# BusPirate-v3_8a-SSOP.net
KiCad netlist of a schematic drawn in EAGLE
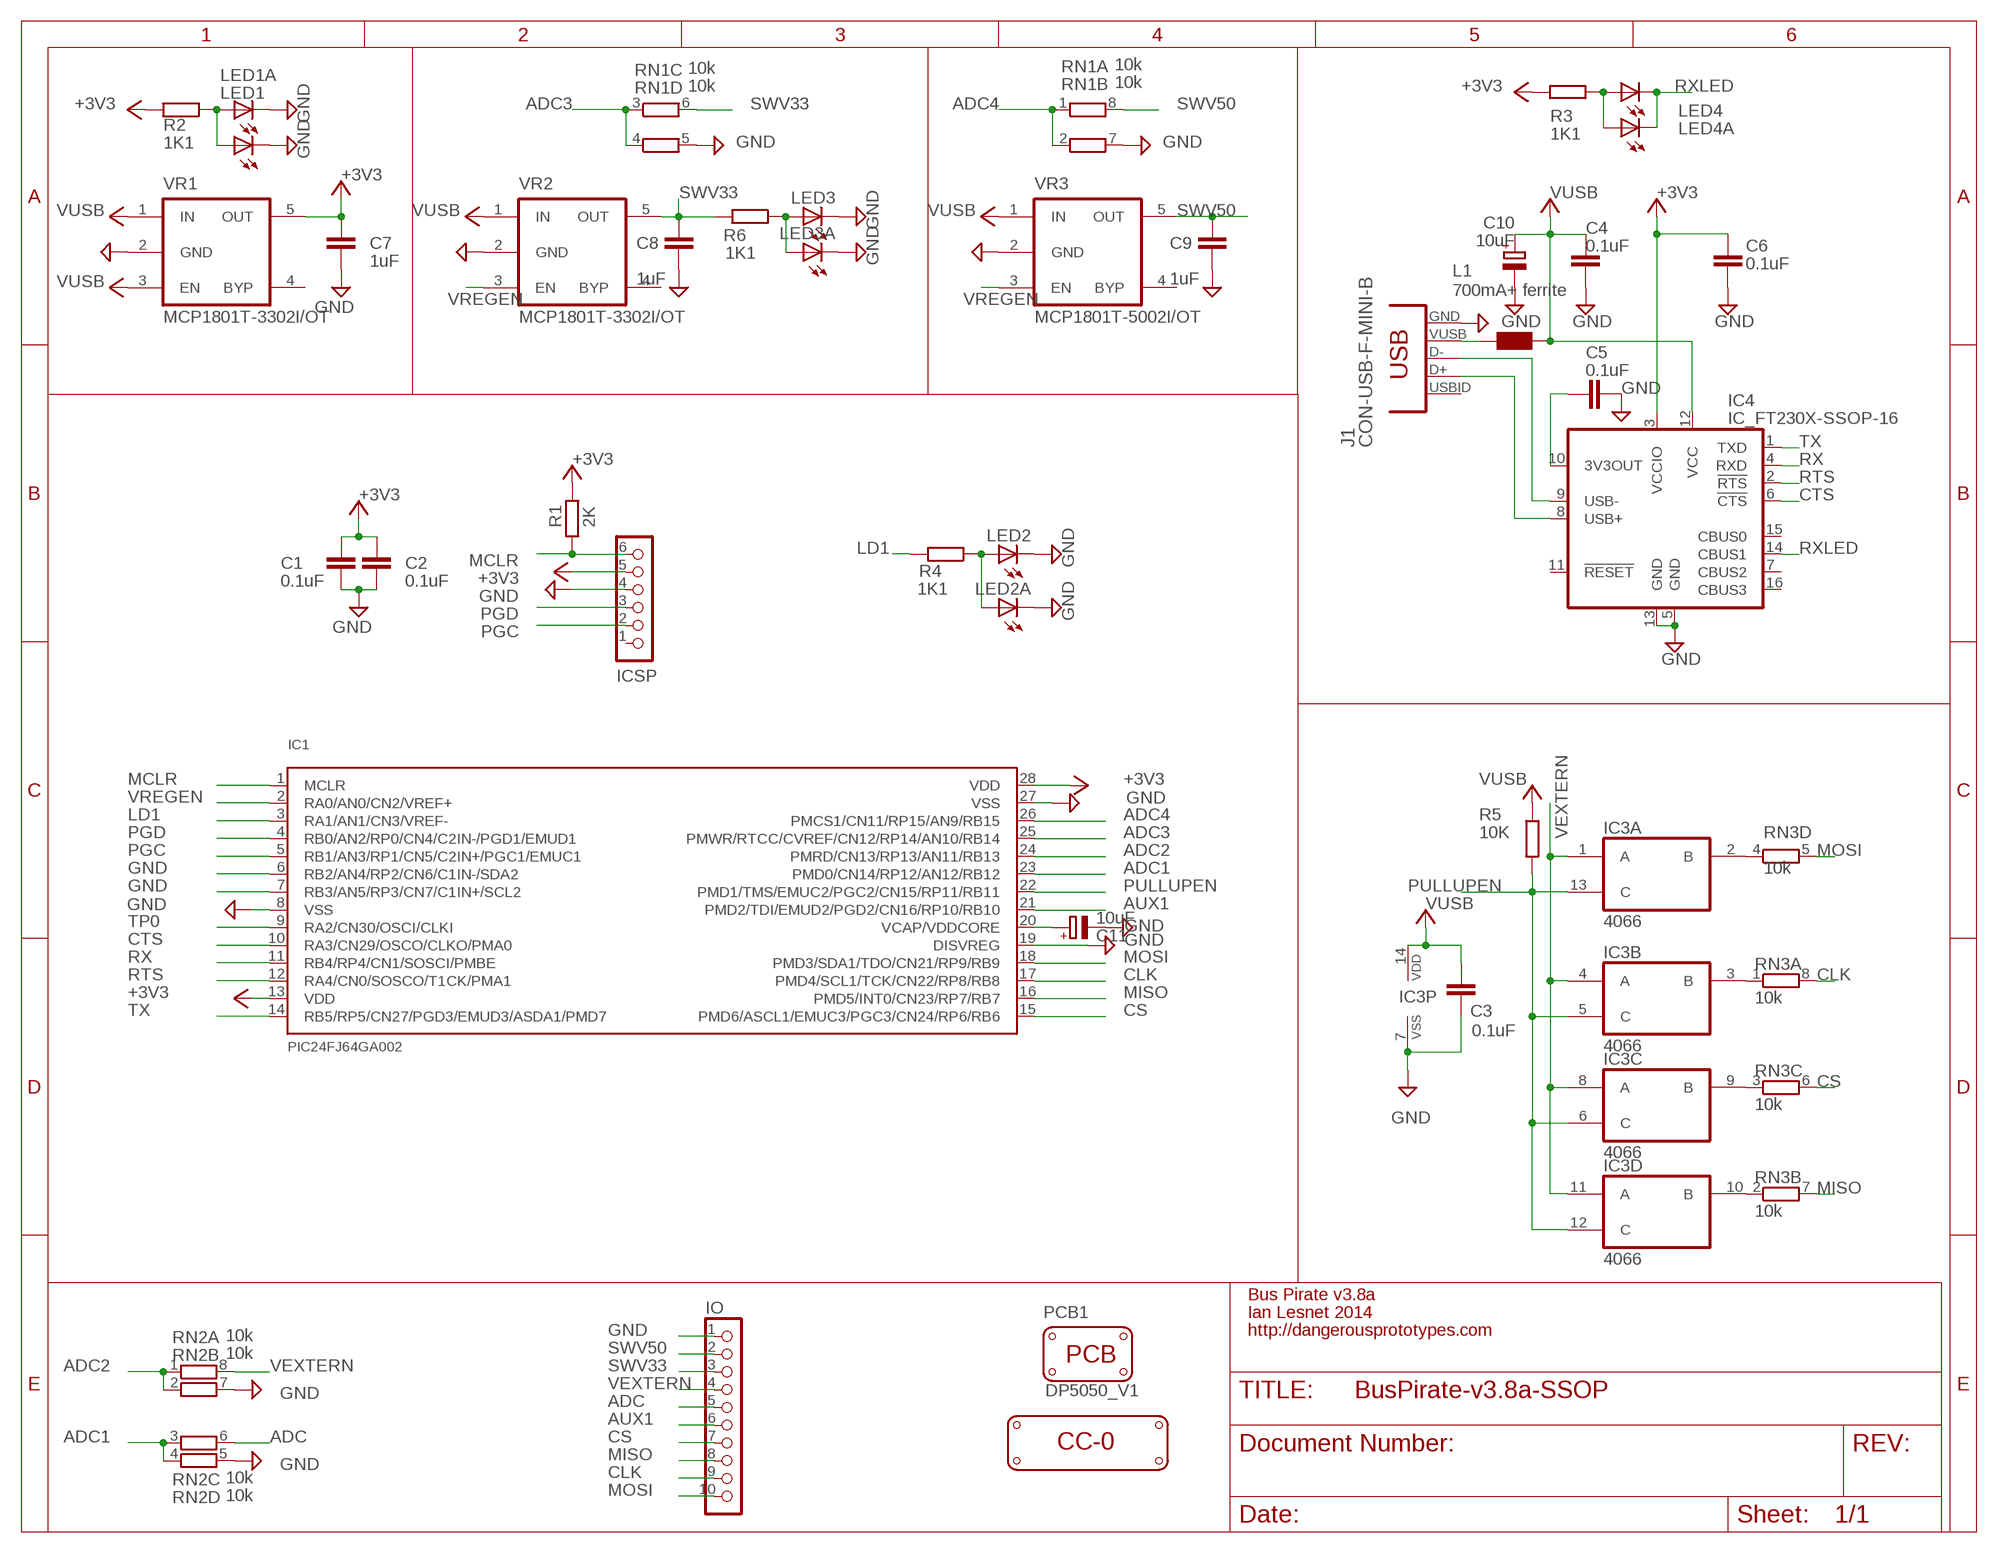
[diagram p0: schematic, sheet 1]

(export (version "E")
  (design (tool "Eeschema 10.0.6"))
  (components
    (comp (ref "C1")
      (value "0.1uF")
      (footprint "eagle-import:C603")
      (libsource (lib "eagle-import") (part "CAPC603"))
    )
    (comp (ref "C2")
      (value "0.1uF")
      (footprint "eagle-import:C603")
      (libsource (lib "eagle-import") (part "CAPC603"))
    )
    (comp (ref "C3")
      (value "0.1uF")
      (footprint "eagle-import:C603")
      (libsource (lib "eagle-import") (part "CAPC603"))
    )
    (comp (ref "C4")
      (value "0.1uF")
      (footprint "eagle-import:C603")
      (libsource (lib "eagle-import") (part "CAPC603"))
    )
    (comp (ref "C5")
      (value "0.1uF")
      (footprint "eagle-import:C603")
      (libsource (lib "eagle-import") (part "CAPC603"))
    )
    (comp (ref "C6")
      (value "0.1uF")
      (footprint "eagle-import:C603")
      (libsource (lib "eagle-import") (part "CAPC603"))
    )
    (comp (ref "C7")
      (value "1uF")
      (footprint "eagle-import:C603")
      (libsource (lib "eagle-import") (part "CAPC603"))
    )
    (comp (ref "C8")
      (value "1uF")
      (footprint "eagle-import:C603")
      (libsource (lib "eagle-import") (part "CAPC603"))
    )
    (comp (ref "C9")
      (value "1uF")
      (footprint "eagle-import:C603")
      (libsource (lib "eagle-import") (part "CAPC603"))
    )
    (comp (ref "C10")
      (value "10uF")
      (footprint "eagle-import:SMC_A")
      (libsource (lib "eagle-import") (part "CPOL-EUSMCA"))
    )
    (comp (ref "C11")
      (value "10uF")
      (footprint "eagle-import:SMC_A")
      (libsource (lib "eagle-import") (part "CPOL-EUSMCA"))
    )
    (comp (ref "IC1")
      (value "PIC24FJ64GA002")
      (footprint "eagle-import:SSOP28")
      (libsource (lib "eagle-import") (part "PIC24FJ64GA002"))
    )
    (comp (ref "IC3")
      (value "4066")
      (footprint "eagle-import:TSSOP14")
      (libsource (lib "eagle-import") (part "4066"))
    )
    (comp (ref "IC4")
      (value "IC_FT230X-SSOP-16")
      (footprint "eagle-import:SSOP-16-FTDI")
      (libsource (lib "eagle-import") (part "IC_FT230X-SSOP-16"))
    )
    (comp (ref "ICSP")
      (value "CON_HEADER_1X06-SMD-RIGHT-ANGLED")
      (footprint "eagle-import:M1X6_MALE_RIGHT_ANGLED_SMD")
      (libsource (lib "eagle-import") (part "CON_HEADER_1X06-SMD-RIGHT-ANGLED"))
    )
    (comp (ref "IO")
      (value "CON_HEADER_1X10-_RIGHTANGLED_SMD")
      (footprint "eagle-import:M1X10_MALE_RIGHT_ANGLED_SMD")
      (libsource (lib "eagle-import") (part "CON_HEADER_1X10-_RIGHTANGLED_SMD"))
    )
    (comp (ref "J1")
      (value "CON-USB-F-MINI-B")
      (footprint "eagle-import:CONN_USB_MINI-B")
      (libsource (lib "eagle-import") (part "CON-USB-F-MINI-B"))
    )
    (comp (ref "L1")
      (value "700mA+ ferrite")
      (footprint "eagle-import:WE-KI_0805_B")
      (libsource (lib "eagle-import") (part "WE-KIL_0805"))
    )
    (comp (ref "LED1")
      (value "LED-0603")
      (footprint "eagle-import:LED-603")
      (libsource (lib "eagle-import") (part "LED-0603"))
    )
    (comp (ref "LED1A")
      (value "LED-0603")
      (footprint "eagle-import:LED-603")
      (libsource (lib "eagle-import") (part "LED-0603"))
    )
    (comp (ref "LED2")
      (value "LED-0603")
      (footprint "eagle-import:LED-603")
      (libsource (lib "eagle-import") (part "LED-0603"))
    )
    (comp (ref "LED2A")
      (value "LED-0603")
      (footprint "eagle-import:LED-603")
      (libsource (lib "eagle-import") (part "LED-0603"))
    )
    (comp (ref "LED3")
      (value "LED-0603")
      (footprint "eagle-import:LED-603")
      (libsource (lib "eagle-import") (part "LED-0603"))
    )
    (comp (ref "LED3A")
      (value "LED-0603")
      (footprint "eagle-import:LED-603")
      (libsource (lib "eagle-import") (part "LED-0603"))
    )
    (comp (ref "LED4")
      (value "LED-0603")
      (footprint "eagle-import:LED-603")
      (libsource (lib "eagle-import") (part "LED-0603"))
    )
    (comp (ref "LED4A")
      (value "LED-0603")
      (footprint "eagle-import:LED-603")
      (libsource (lib "eagle-import") (part "LED-0603"))
    )
    (comp (ref "LOGO1")
      (value "LOGO_CC-0")
      (footprint "eagle-import:LOGO_CC-0")
      (libsource (lib "eagle-import") (part "LOGO_CC-0"))
    )
    (comp (ref "PCB1")
      (value "PCB_DP_SQUARE-5X5")
      (footprint "eagle-import:DP5050_V1")
      (libsource (lib "eagle-import") (part "PCB_DP_SQUARE-5X5"))
    )
    (comp (ref "R1")
      (value "2K")
      (footprint "eagle-import:R603")
      (libsource (lib "eagle-import") (part "RESISTORR603"))
    )
    (comp (ref "R2")
      (value "1K1")
      (footprint "eagle-import:R603")
      (libsource (lib "eagle-import") (part "RESISTORR603"))
    )
    (comp (ref "R3")
      (value "1K1")
      (footprint "eagle-import:R603")
      (libsource (lib "eagle-import") (part "RESISTORR603"))
    )
    (comp (ref "R4")
      (value "1K1")
      (footprint "eagle-import:R603")
      (libsource (lib "eagle-import") (part "RESISTORR603"))
    )
    (comp (ref "R5")
      (value "10K")
      (footprint "eagle-import:R603")
      (libsource (lib "eagle-import") (part "RESISTORR603"))
    )
    (comp (ref "R6")
      (value "1K1")
      (footprint "eagle-import:R603")
      (libsource (lib "eagle-import") (part "RESISTORR603"))
    )
    (comp (ref "RN1")
      (value "10k")
      (footprint "eagle-import:RN8P-4R-CRA06S")
      (libsource (lib "eagle-import") (part "RNETWORK"))
    )
    (comp (ref "RN2")
      (value "10k")
      (footprint "eagle-import:RN8P-4R-CRA06S")
      (libsource (lib "eagle-import") (part "RNETWORK"))
    )
    (comp (ref "RN3")
      (value "10k")
      (footprint "eagle-import:RN8P-4R-CRA06S")
      (libsource (lib "eagle-import") (part "RNETWORK"))
    )
    (comp (ref "VR1")
      (value "MCP1801T-3302I/OT")
      (footprint "eagle-import:SOT-23-5")
      (libsource (lib "eagle-import") (part "MIC5205"))
    )
    (comp (ref "VR2")
      (value "MCP1801T-3302I/OT")
      (footprint "eagle-import:SOT-23-5")
      (libsource (lib "eagle-import") (part "MIC5205"))
    )
    (comp (ref "VR3")
      (value "MCP1801T-5002I/OT")
      (footprint "eagle-import:SOT-23-5")
      (libsource (lib "eagle-import") (part "MIC5205"))
    )
  )
  (nets
    (net (code "1") (name "/ADC") (class "Default")
      (node (ref "IO") (pin "5") (pinfunction "5_5") (pintype "passive"))
      (node (ref "RN2") (pin "6") (pinfunction "2_6") (pintype "passive"))
    )
    (net (code "2") (name "/ADC1") (class "Default")
      (node (ref "IC1") (pin "23") (pinfunction "PMD0/CN14/RP12/AN12/RB12_23") (pintype "bidirectional"))
      (node (ref "RN2") (pin "3") (pinfunction "1_3") (pintype "passive"))
      (node (ref "RN2") (pin "4") (pinfunction "1_4") (pintype "passive"))
    )
    (net (code "3") (name "/ADC2") (class "Default")
      (node (ref "IC1") (pin "24") (pinfunction "PMRD/CN13/RP13/AN11/RB13_24") (pintype "bidirectional"))
      (node (ref "RN2") (pin "1") (pinfunction "1_1") (pintype "passive"))
      (node (ref "RN2") (pin "2") (pinfunction "1_2") (pintype "passive"))
    )
    (net (code "4") (name "/ADC3") (class "Default")
      (node (ref "IC1") (pin "25") (pinfunction "PMWR/RTCC/CVREF/CN12/RP14/AN10/RB14_25") (pintype "bidirectional"))
      (node (ref "RN1") (pin "3") (pinfunction "1_3") (pintype "passive"))
      (node (ref "RN1") (pin "4") (pinfunction "1_4") (pintype "passive"))
    )
    (net (code "5") (name "/ADC4") (class "Default")
      (node (ref "IC1") (pin "26") (pinfunction "PMCS1/CN11/RP15/AN9/RB15_26") (pintype "bidirectional"))
      (node (ref "RN1") (pin "1") (pinfunction "1_1") (pintype "passive"))
      (node (ref "RN1") (pin "2") (pinfunction "1_2") (pintype "passive"))
    )
    (net (code "6") (name "/AUX1") (class "Default")
      (node (ref "IC1") (pin "21") (pinfunction "PMD2/TDI/EMUD2/PGD2/CN16/RP10/RB10_21") (pintype "bidirectional"))
      (node (ref "IO") (pin "6") (pinfunction "6_6") (pintype "passive"))
    )
    (net (code "7") (name "/CLK") (class "Default")
      (node (ref "IC1") (pin "17") (pinfunction "PMD4/SCL1/TCK/CN22/RP8/RB8_17") (pintype "bidirectional"))
      (node (ref "IO") (pin "9") (pinfunction "9_9") (pintype "passive"))
      (node (ref "RN3") (pin "8") (pinfunction "2_8") (pintype "passive"))
    )
    (net (code "8") (name "/CS") (class "Default")
      (node (ref "IC1") (pin "15") (pinfunction "PMD6/ASCL1/EMUC3/PGC3/CN24/RP6/RB6_15") (pintype "bidirectional"))
      (node (ref "IO") (pin "7") (pinfunction "7_7") (pintype "passive"))
      (node (ref "RN3") (pin "6") (pinfunction "2_6") (pintype "passive"))
    )
    (net (code "9") (name "/CTS") (class "Default")
      (node (ref "IC1") (pin "10") (pinfunction "RA3/CN29/OSCO/CLKO/PMA0_10") (pintype "bidirectional"))
      (node (ref "IC4") (pin "6") (pinfunction "~{CTS}_6") (pintype "bidirectional"))
    )
    (net (code "10") (name "/LD1") (class "Default")
      (node (ref "IC1") (pin "3") (pinfunction "RA1/AN1/CN3/VREF-_3") (pintype "bidirectional"))
      (node (ref "R4") (pin "2") (pinfunction "2_2") (pintype "passive"))
    )
    (net (code "11") (name "/MCLR") (class "Default")
      (node (ref "IC1") (pin "1") (pinfunction "MCLR_1") (pintype "input"))
      (node (ref "ICSP") (pin "6") (pinfunction "6_6") (pintype "passive"))
      (node (ref "R1") (pin "1") (pinfunction "1_1") (pintype "passive"))
    )
    (net (code "12") (name "/MISO") (class "Default")
      (node (ref "IC1") (pin "16") (pinfunction "PMD5/INT0/CN23/RP7/RB7_16") (pintype "bidirectional"))
      (node (ref "IO") (pin "8") (pinfunction "8_8") (pintype "passive"))
      (node (ref "RN3") (pin "7") (pinfunction "2_7") (pintype "passive"))
    )
    (net (code "13") (name "/MOSI") (class "Default")
      (node (ref "IC1") (pin "18") (pinfunction "PMD3/SDA1/TDO/CN21/RP9/RB9_18") (pintype "bidirectional"))
      (node (ref "IO") (pin "10") (pinfunction "10_10") (pintype "passive"))
      (node (ref "RN3") (pin "5") (pinfunction "2_5") (pintype "passive"))
    )
    (net (code "14") (name "/PGC") (class "Default")
      (node (ref "IC1") (pin "5") (pinfunction "RB1/AN3/RP1/CN5/C2IN+/PGC1/EMUC1_5") (pintype "bidirectional"))
      (node (ref "ICSP") (pin "2") (pinfunction "2_2") (pintype "bidirectional"))
    )
    (net (code "15") (name "/PGD") (class "Default")
      (node (ref "IC1") (pin "4") (pinfunction "RB0/AN2/RP0/CN4/C2IN-/PGD1/EMUD1_4") (pintype "bidirectional"))
      (node (ref "ICSP") (pin "3") (pinfunction "3_3") (pintype "passive"))
    )
    (net (code "16") (name "/PULLUPEN") (class "Default")
      (node (ref "IC1") (pin "22") (pinfunction "PMD1/TMS/EMUC2/PGC2/CN15/RP11/RB11_22") (pintype "bidirectional"))
      (node (ref "IC3") (pin "12") (pinfunction "C_12") (pintype "input"))
      (node (ref "IC3") (pin "13") (pinfunction "C_13") (pintype "input"))
      (node (ref "IC3") (pin "5") (pinfunction "C_5") (pintype "input"))
      (node (ref "IC3") (pin "6") (pinfunction "C_6") (pintype "input"))
      (node (ref "R5") (pin "2") (pinfunction "2_2") (pintype "passive"))
    )
    (net (code "17") (name "/RTS") (class "Default")
      (node (ref "IC1") (pin "12") (pinfunction "RA4/CN0/SOSCO/T1CK/PMA1_12") (pintype "bidirectional"))
      (node (ref "IC4") (pin "2") (pinfunction "~{RTS}_2") (pintype "bidirectional"))
    )
    (net (code "18") (name "/RX") (class "Default")
      (node (ref "IC1") (pin "11") (pinfunction "RB4/RP4/CN1/SOSCI/PMBE_11") (pintype "bidirectional"))
      (node (ref "IC4") (pin "4") (pinfunction "RXD_4") (pintype "input"))
    )
    (net (code "19") (name "/RXLED") (class "Default")
      (node (ref "IC4") (pin "14") (pinfunction "CBUS1_14") (pintype "bidirectional"))
      (node (ref "LED4") (pin "C") (pinfunction "C_C") (pintype "passive"))
      (node (ref "LED4A") (pin "C") (pinfunction "C_C") (pintype "passive"))
    )
    (net (code "20") (name "/SWV33") (class "Default")
      (node (ref "C8") (pin "1") (pinfunction "1_1") (pintype "passive"))
      (node (ref "IO") (pin "3") (pinfunction "3_3") (pintype "passive"))
      (node (ref "R6") (pin "2") (pinfunction "2_2") (pintype "passive"))
      (node (ref "RN1") (pin "6") (pinfunction "2_6") (pintype "passive"))
      (node (ref "VR2") (pin "5") (pinfunction "OUT_5") (pintype "bidirectional"))
    )
    (net (code "21") (name "/SWV50") (class "Default")
      (node (ref "C9") (pin "1") (pinfunction "1_1") (pintype "passive"))
      (node (ref "IO") (pin "2") (pinfunction "2_2") (pintype "passive"))
      (node (ref "RN1") (pin "8") (pinfunction "2_8") (pintype "passive"))
      (node (ref "VR3") (pin "5") (pinfunction "OUT_5") (pintype "bidirectional"))
    )
    (net (code "22") (name "/TP0") (class "Default")
      (node (ref "IC1") (pin "9") (pinfunction "RA2/CN30/OSCI/CLKI_9") (pintype "bidirectional"))
    )
    (net (code "23") (name "/TX") (class "Default")
      (node (ref "IC1") (pin "14") (pinfunction "RB5/RP5/CN27/PGD3/EMUD3/ASDA1/PMD7_14") (pintype "bidirectional"))
      (node (ref "IC4") (pin "1") (pinfunction "TXD_1") (pintype "output"))
    )
    (net (code "24") (name "/VEXTERN") (class "Default")
      (node (ref "IC3") (pin "1") (pinfunction "A_1") (pintype "tri_state"))
      (node (ref "IC3") (pin "11") (pinfunction "A_11") (pintype "tri_state"))
      (node (ref "IC3") (pin "4") (pinfunction "A_4") (pintype "tri_state"))
      (node (ref "IC3") (pin "8") (pinfunction "A_8") (pintype "tri_state"))
      (node (ref "IO") (pin "4") (pinfunction "4_4") (pintype "passive"))
      (node (ref "RN2") (pin "8") (pinfunction "2_8") (pintype "passive"))
    )
    (net (code "25") (name "/VREGEN") (class "Default")
      (node (ref "IC1") (pin "2") (pinfunction "RA0/AN0/CN2/VREF+_2") (pintype "bidirectional"))
      (node (ref "VR2") (pin "3") (pinfunction "EN_3") (pintype "bidirectional"))
      (node (ref "VR3") (pin "3") (pinfunction "EN_3") (pintype "bidirectional"))
    )
    (net (code "26") (name "GND") (class "Default")
      (node (ref "C1") (pin "2") (pinfunction "2_2") (pintype "passive"))
      (node (ref "C10") (pin "-") (pinfunction "-_-") (pintype "passive"))
      (node (ref "C11") (pin "-") (pinfunction "-_-") (pintype "passive"))
      (node (ref "C2") (pin "2") (pinfunction "2_2") (pintype "passive"))
      (node (ref "C3") (pin "2") (pinfunction "2_2") (pintype "passive"))
      (node (ref "C4") (pin "2") (pinfunction "2_2") (pintype "passive"))
      (node (ref "C5") (pin "2") (pinfunction "2_2") (pintype "passive"))
      (node (ref "C6") (pin "2") (pinfunction "2_2") (pintype "passive"))
      (node (ref "C7") (pin "2") (pinfunction "2_2") (pintype "passive"))
      (node (ref "C8") (pin "2") (pinfunction "2_2") (pintype "passive"))
      (node (ref "C9") (pin "2") (pinfunction "2_2") (pintype "passive"))
      (node (ref "IC1") (pin "19") (pinfunction "DISVREG_19") (pintype "power_in"))
      (node (ref "IC1") (pin "27") (pinfunction "VSS_27") (pintype "power_in"))
      (node (ref "IC1") (pin "6") (pinfunction "RB2/AN4/RP2/CN6/C1IN-/SDA2_6") (pintype "bidirectional"))
      (node (ref "IC1") (pin "7") (pinfunction "RB3/AN5/RP3/CN7/C1IN+/SCL2_7") (pintype "bidirectional"))
      (node (ref "IC1") (pin "8") (pinfunction "VSS_8") (pintype "power_in"))
      (node (ref "IC3") (pin "7") (pinfunction "VSS_7") (pintype "power_in"))
      (node (ref "IC4") (pin "13") (pinfunction "GND_13") (pintype "power_in"))
      (node (ref "IC4") (pin "5") (pinfunction "GND_5") (pintype "power_in"))
      (node (ref "ICSP") (pin "4") (pinfunction "4_4") (pintype "passive"))
      (node (ref "IO") (pin "1") (pinfunction "1_1") (pintype "passive"))
      (node (ref "J1") (pin "GND") (pinfunction "GND_GND") (pintype "bidirectional"))
      (node (ref "LED1") (pin "C") (pinfunction "C_C") (pintype "passive"))
      (node (ref "LED1A") (pin "C") (pinfunction "C_C") (pintype "passive"))
      (node (ref "LED2") (pin "C") (pinfunction "C_C") (pintype "passive"))
      (node (ref "LED2A") (pin "C") (pinfunction "C_C") (pintype "passive"))
      (node (ref "LED3") (pin "C") (pinfunction "C_C") (pintype "passive"))
      (node (ref "LED3A") (pin "C") (pinfunction "C_C") (pintype "passive"))
      (node (ref "RN1") (pin "5") (pinfunction "2_5") (pintype "passive"))
      (node (ref "RN1") (pin "7") (pinfunction "2_7") (pintype "passive"))
      (node (ref "RN2") (pin "5") (pinfunction "2_5") (pintype "passive"))
      (node (ref "RN2") (pin "7") (pinfunction "2_7") (pintype "passive"))
      (node (ref "VR1") (pin "2") (pinfunction "GND_2") (pintype "bidirectional"))
      (node (ref "VR2") (pin "2") (pinfunction "GND_2") (pintype "bidirectional"))
      (node (ref "VR3") (pin "2") (pinfunction "GND_2") (pintype "bidirectional"))
    )
    (net (code "27") (name "Net-(IC1-VCAP{slash}VDDCORE)") (class "Default")
      (node (ref "C11") (pin "+") (pinfunction "+_+") (pintype "passive"))
      (node (ref "IC1") (pin "20") (pinfunction "VCAP/VDDCORE_20") (pintype "power_in"))
    )
    (net (code "28") (name "Net-(IC3A-B)") (class "Default")
      (node (ref "IC3") (pin "2") (pinfunction "B_2") (pintype "tri_state"))
      (node (ref "RN3") (pin "4") (pinfunction "1_4") (pintype "passive"))
    )
    (net (code "29") (name "Net-(IC3B-B)") (class "Default")
      (node (ref "IC3") (pin "3") (pinfunction "B_3") (pintype "tri_state"))
      (node (ref "RN3") (pin "1") (pinfunction "1_1") (pintype "passive"))
    )
    (net (code "30") (name "Net-(IC3C-B)") (class "Default")
      (node (ref "IC3") (pin "9") (pinfunction "B_9") (pintype "tri_state"))
      (node (ref "RN3") (pin "3") (pinfunction "1_3") (pintype "passive"))
    )
    (net (code "31") (name "Net-(IC3D-B)") (class "Default")
      (node (ref "IC3") (pin "10") (pinfunction "B_10") (pintype "tri_state"))
      (node (ref "RN3") (pin "2") (pinfunction "1_2") (pintype "passive"))
    )
    (net (code "32") (name "Net-(IC4-3V3OUT)") (class "Default")
      (node (ref "C5") (pin "1") (pinfunction "1_1") (pintype "passive"))
      (node (ref "IC4") (pin "10") (pinfunction "3V3OUT_10") (pintype "power_in"))
    )
    (net (code "33") (name "Net-(IC4-USB+)") (class "Default")
      (node (ref "IC4") (pin "8") (pinfunction "USB+_8") (pintype "output"))
      (node (ref "J1") (pin "D+") (pinfunction "D+_D+") (pintype "bidirectional"))
    )
    (net (code "34") (name "Net-(IC4-USB-)") (class "Default")
      (node (ref "IC4") (pin "9") (pinfunction "USB-_9") (pintype "input"))
      (node (ref "J1") (pin "D-") (pinfunction "D-_D-") (pintype "bidirectional"))
    )
    (net (code "35") (name "Net-(L1-1)") (class "Default")
      (node (ref "J1") (pin "VUSB") (pinfunction "VUSB_VUSB") (pintype "bidirectional"))
      (node (ref "L1") (pin "2") (pinfunction "1_2") (pintype "passive"))
    )
    (net (code "36") (name "Net-(LED1-PadA)") (class "Default")
      (node (ref "LED1") (pin "A") (pinfunction "A_A") (pintype "passive"))
      (node (ref "LED1A") (pin "A") (pinfunction "A_A") (pintype "passive"))
      (node (ref "R2") (pin "1") (pinfunction "1_1") (pintype "passive"))
    )
    (net (code "37") (name "Net-(LED2-PadA)") (class "Default")
      (node (ref "LED2") (pin "A") (pinfunction "A_A") (pintype "passive"))
      (node (ref "LED2A") (pin "A") (pinfunction "A_A") (pintype "passive"))
      (node (ref "R4") (pin "1") (pinfunction "1_1") (pintype "passive"))
    )
    (net (code "38") (name "Net-(LED3-PadA)") (class "Default")
      (node (ref "LED3") (pin "A") (pinfunction "A_A") (pintype "passive"))
      (node (ref "LED3A") (pin "A") (pinfunction "A_A") (pintype "passive"))
      (node (ref "R6") (pin "1") (pinfunction "1_1") (pintype "passive"))
    )
    (net (code "39") (name "Net-(LED4-PadA)") (class "Default")
      (node (ref "LED4") (pin "A") (pinfunction "A_A") (pintype "passive"))
      (node (ref "LED4A") (pin "A") (pinfunction "A_A") (pintype "passive"))
      (node (ref "R3") (pin "1") (pinfunction "1_1") (pintype "passive"))
    )
    (net (code "40") (name "SUPPLY_+3V3") (class "Default")
      (node (ref "C1") (pin "1") (pinfunction "1_1") (pintype "passive"))
      (node (ref "C2") (pin "1") (pinfunction "1_1") (pintype "passive"))
      (node (ref "C6") (pin "1") (pinfunction "1_1") (pintype "passive"))
      (node (ref "C7") (pin "1") (pinfunction "1_1") (pintype "passive"))
      (node (ref "IC1") (pin "13") (pinfunction "VDD_13") (pintype "power_in"))
      (node (ref "IC1") (pin "28") (pinfunction "VDD_28") (pintype "power_in"))
      (node (ref "IC4") (pin "3") (pinfunction "VCCIO_3") (pintype "power_in"))
      (node (ref "ICSP") (pin "5") (pinfunction "5_5") (pintype "passive"))
      (node (ref "R1") (pin "2") (pinfunction "2_2") (pintype "passive"))
      (node (ref "R2") (pin "2") (pinfunction "2_2") (pintype "passive"))
      (node (ref "R3") (pin "2") (pinfunction "2_2") (pintype "passive"))
      (node (ref "VR1") (pin "5") (pinfunction "OUT_5") (pintype "bidirectional"))
    )
    (net (code "41") (name "SUPPLY_VUSB") (class "Default")
      (node (ref "C10") (pin "+") (pinfunction "+_+") (pintype "passive"))
      (node (ref "C3") (pin "1") (pinfunction "1_1") (pintype "passive"))
      (node (ref "C4") (pin "1") (pinfunction "1_1") (pintype "passive"))
      (node (ref "IC3") (pin "14") (pinfunction "VDD_14") (pintype "power_in"))
      (node (ref "IC4") (pin "12") (pinfunction "VCC_12") (pintype "power_in"))
      (node (ref "L1") (pin "1") (pinfunction "2_1") (pintype "passive"))
      (node (ref "R5") (pin "1") (pinfunction "1_1") (pintype "passive"))
      (node (ref "VR1") (pin "1") (pinfunction "IN_1") (pintype "bidirectional"))
      (node (ref "VR1") (pin "3") (pinfunction "EN_3") (pintype "bidirectional"))
      (node (ref "VR2") (pin "1") (pinfunction "IN_1") (pintype "bidirectional"))
      (node (ref "VR3") (pin "1") (pinfunction "IN_1") (pintype "bidirectional"))
    )
    (net (code "42") (name "unconnected-(IC4-CBUS0-Pad15)") (class "Default")
      (node (ref "IC4") (pin "15") (pinfunction "CBUS0_15") (pintype "bidirectional"))
    )
    (net (code "43") (name "unconnected-(IC4-CBUS2-Pad7)") (class "Default")
      (node (ref "IC4") (pin "7") (pinfunction "CBUS2_7") (pintype "bidirectional"))
    )
    (net (code "44") (name "unconnected-(IC4-CBUS3-Pad16)") (class "Default")
      (node (ref "IC4") (pin "16") (pinfunction "CBUS3_16") (pintype "bidirectional"))
    )
    (net (code "45") (name "unconnected-(IC4-~{RESET}-Pad11)") (class "Default")
      (node (ref "IC4") (pin "11") (pinfunction "~{RESET}_11") (pintype "bidirectional"))
    )
    (net (code "46") (name "unconnected-(ICSP-Pad1)") (class "Default")
      (node (ref "ICSP") (pin "1") (pinfunction "1_1") (pintype "bidirectional"))
    )
    (net (code "47") (name "unconnected-(J1B-USBID-PadID)") (class "Default")
      (node (ref "J1") (pin "ID") (pinfunction "USBID_ID") (pintype "bidirectional"))
    )
    (net (code "48") (name "unconnected-(VR1-BYP-Pad4)") (class "Default")
      (node (ref "VR1") (pin "4") (pinfunction "BYP_4") (pintype "bidirectional"))
    )
    (net (code "49") (name "unconnected-(VR2-BYP-Pad4)") (class "Default")
      (node (ref "VR2") (pin "4") (pinfunction "BYP_4") (pintype "bidirectional"))
    )
    (net (code "50") (name "unconnected-(VR3-BYP-Pad4)") (class "Default")
      (node (ref "VR3") (pin "4") (pinfunction "BYP_4") (pintype "bidirectional"))
    )
  )
)
